# CATS-Vega-USB.net
KiCad netlist of a schematic drawn in Altium Designer
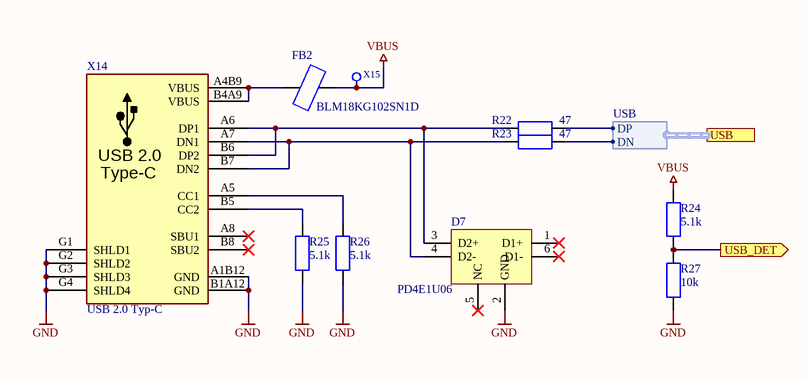
[diagram p0: CATS-Vega-USB.SchDoc]

(export (version "E")
  (design (tool "Eeschema 10.0.6"))
  (components
    (comp (ref "D7")
      (value "PD4E1U06")
      (footprint "SMD IC SOT-363 (SC-70-6)")
      (description "Unidirectional 3A (8/20us) 15V (Typ) 6.5V 5.5V (Max) SOT-363 ESD Protection Devices ROHS")
      (libsource (lib "Other") (part "PD4E1U06DCKR"))
    )
    (comp (ref "FB2")
      (value "BLM18KG102SN1D")
      (footprint "SMD Ferrite Bead 0603")
      (description "1 kOhms @ 100MHz 1 Power Line Ferrite Bead 0603 (1608 Metric) 1A 200mOhm")
      (libsource (lib "CATS-EUROC") (part "BLM18KG102SN1D"))
    )
    (comp (ref "R22")
      (value "47")
      (footprint "SMD Widerstand 0603")
      (description "SMD Chip Resistor E24")
      (libsource (lib "Resistors-E24") (part "E24 - 47"))
    )
    (comp (ref "R23")
      (value "47")
      (footprint "SMD Widerstand 0603")
      (description "SMD Chip Resistor E24")
      (libsource (lib "Resistors-E24") (part "E24 - 47"))
    )
    (comp (ref "R24")
      (value "5.1k")
      (footprint "SMD Widerstand 0603")
      (description "SMD Chip Resistor E24")
      (libsource (lib "CATS-EUROC") (part "E24 - 5.1k"))
    )
    (comp (ref "R25")
      (value "5.1k")
      (footprint "SMD Widerstand 0603")
      (description "SMD Chip Resistor E24")
      (libsource (lib "") (part "E24 - 5.1k_1"))
    )
    (comp (ref "R26")
      (value "5.1k")
      (footprint "SMD Widerstand 0603")
      (description "SMD Chip Resistor E24")
      (libsource (lib "") (part "E24 - 5.1k_1"))
    )
    (comp (ref "R27")
      (value "10k")
      (footprint "SMD Widerstand 0603")
      (description "SMD Chip Resistor E24")
      (libsource (lib "CATS-EUROC") (part "E24 - 10k"))
    )
    (comp (ref "X14")
      (value "USB 2.0 Typ-C")
      (footprint "THT USB-C Socket (A40-00119)")
      (description "Typ-C")
      (libsource (lib "CATS-EUROC") (part "USB Type-C USB 2.0"))
    )
    (comp (ref "X15")
      (value "-")
      (footprint "SMD Test point 0.8mm")
      (description "Test Point SMD")
      (libsource (lib "Connectors") (part "SMD Test point"))
    )
  )
  (nets
    (net (code "2") (name "/DN") (class "Default")
      (node (ref "R23") (pin "2") (pinfunction "2_2") (pintype "passive"))
    )
    (net (code "3") (name "/DP") (class "Default")
      (node (ref "R22") (pin "2") (pinfunction "2_2") (pintype "passive"))
    )
    (net (code "4") (name "/USB_DET") (class "Default")
      (node (ref "R24") (pin "2") (pinfunction "2_2") (pintype "passive"))
      (node (ref "R27") (pin "1") (pinfunction "1_1") (pintype "passive"))
    )
    (net (code "6") (name "GND") (class "Default")
      (node (ref "D7") (pin "2") (pinfunction "GND_2") (pintype "passive"))
      (node (ref "R25") (pin "1") (pinfunction "1_1") (pintype "passive"))
      (node (ref "R26") (pin "1") (pinfunction "1_1") (pintype "passive"))
      (node (ref "R27") (pin "2") (pinfunction "2_2") (pintype "passive"))
      (node (ref "X14") (pin "A1B12") (pinfunction "GND_A1B12") (pintype "passive"))
      (node (ref "X14") (pin "B1A12") (pinfunction "GND_B1A12") (pintype "passive"))
      (node (ref "X14") (pin "G1") (pinfunction "SHLD1_G1") (pintype "passive"))
      (node (ref "X14") (pin "G2") (pinfunction "SHLD2_G2") (pintype "passive"))
      (node (ref "X14") (pin "G3") (pinfunction "SHLD3_G3") (pintype "passive"))
      (node (ref "X14") (pin "G4") (pinfunction "SHLD4_G4") (pintype "passive"))
    )
    (net (code "7") (name "Net-(D7-D2+)") (class "Default")
      (node (ref "D7") (pin "3") (pinfunction "D2+_3") (pintype "passive"))
      (node (ref "R22") (pin "1") (pinfunction "1_1") (pintype "passive"))
      (node (ref "X14") (pin "A6") (pinfunction "DP1_A6") (pintype "passive"))
      (node (ref "X14") (pin "B6") (pinfunction "DP2_B6") (pintype "passive"))
    )
    (net (code "8") (name "Net-(D7-D2-)") (class "Default")
      (node (ref "D7") (pin "4") (pinfunction "D2-_4") (pintype "passive"))
      (node (ref "R23") (pin "1") (pinfunction "1_1") (pintype "passive"))
      (node (ref "X14") (pin "A7") (pinfunction "DN1_A7") (pintype "passive"))
      (node (ref "X14") (pin "B7") (pinfunction "DN2_B7") (pintype "passive"))
    )
    (net (code "9") (name "Net-(FB2-Pad2)") (class "Default")
      (node (ref "FB2") (pin "2") (pinfunction "2_2") (pintype "passive"))
      (node (ref "X14") (pin "A4B9") (pinfunction "VBUS_A4B9") (pintype "passive"))
      (node (ref "X14") (pin "B4A9") (pinfunction "VBUS_B4A9") (pintype "passive"))
    )
    (net (code "10") (name "Net-(X14-CC1)") (class "Default")
      (node (ref "R26") (pin "2") (pinfunction "2_2") (pintype "passive"))
      (node (ref "X14") (pin "A5") (pinfunction "CC1_A5") (pintype "passive"))
    )
    (net (code "11") (name "Net-(X14-CC2)") (class "Default")
      (node (ref "R25") (pin "2") (pinfunction "2_2") (pintype "passive"))
      (node (ref "X14") (pin "B5") (pinfunction "CC2_B5") (pintype "passive"))
    )
    (net (code "12") (name "VBUS") (class "Default")
      (node (ref "FB2") (pin "1") (pinfunction "1_1") (pintype "passive"))
      (node (ref "R24") (pin "1") (pinfunction "1_1") (pintype "passive"))
      (node (ref "X15") (pin "1") (pinfunction "1_1") (pintype "passive"))
    )
    (net (code "13") (name "unconnected-(D7-D1+-Pad1)") (class "Default")
      (node (ref "D7") (pin "1") (pinfunction "D1+_1") (pintype "passive+no_connect"))
    )
    (net (code "14") (name "unconnected-(D7-D1--Pad6)") (class "Default")
      (node (ref "D7") (pin "6") (pinfunction "D1-_6") (pintype "passive+no_connect"))
    )
    (net (code "15") (name "unconnected-(D7-NC-Pad5)") (class "Default")
      (node (ref "D7") (pin "5") (pinfunction "NC_5") (pintype "passive+no_connect"))
    )
    (net (code "16") (name "unconnected-(X14-SBU1-PadA8)") (class "Default")
      (node (ref "X14") (pin "A8") (pinfunction "SBU1_A8") (pintype "passive+no_connect"))
    )
    (net (code "17") (name "unconnected-(X14-SBU2-PadB8)") (class "Default")
      (node (ref "X14") (pin "B8") (pinfunction "SBU2_B8") (pintype "passive+no_connect"))
    )
  )
)
